# lm386.net
KiCad netlist of a schematic drawn in EAGLE
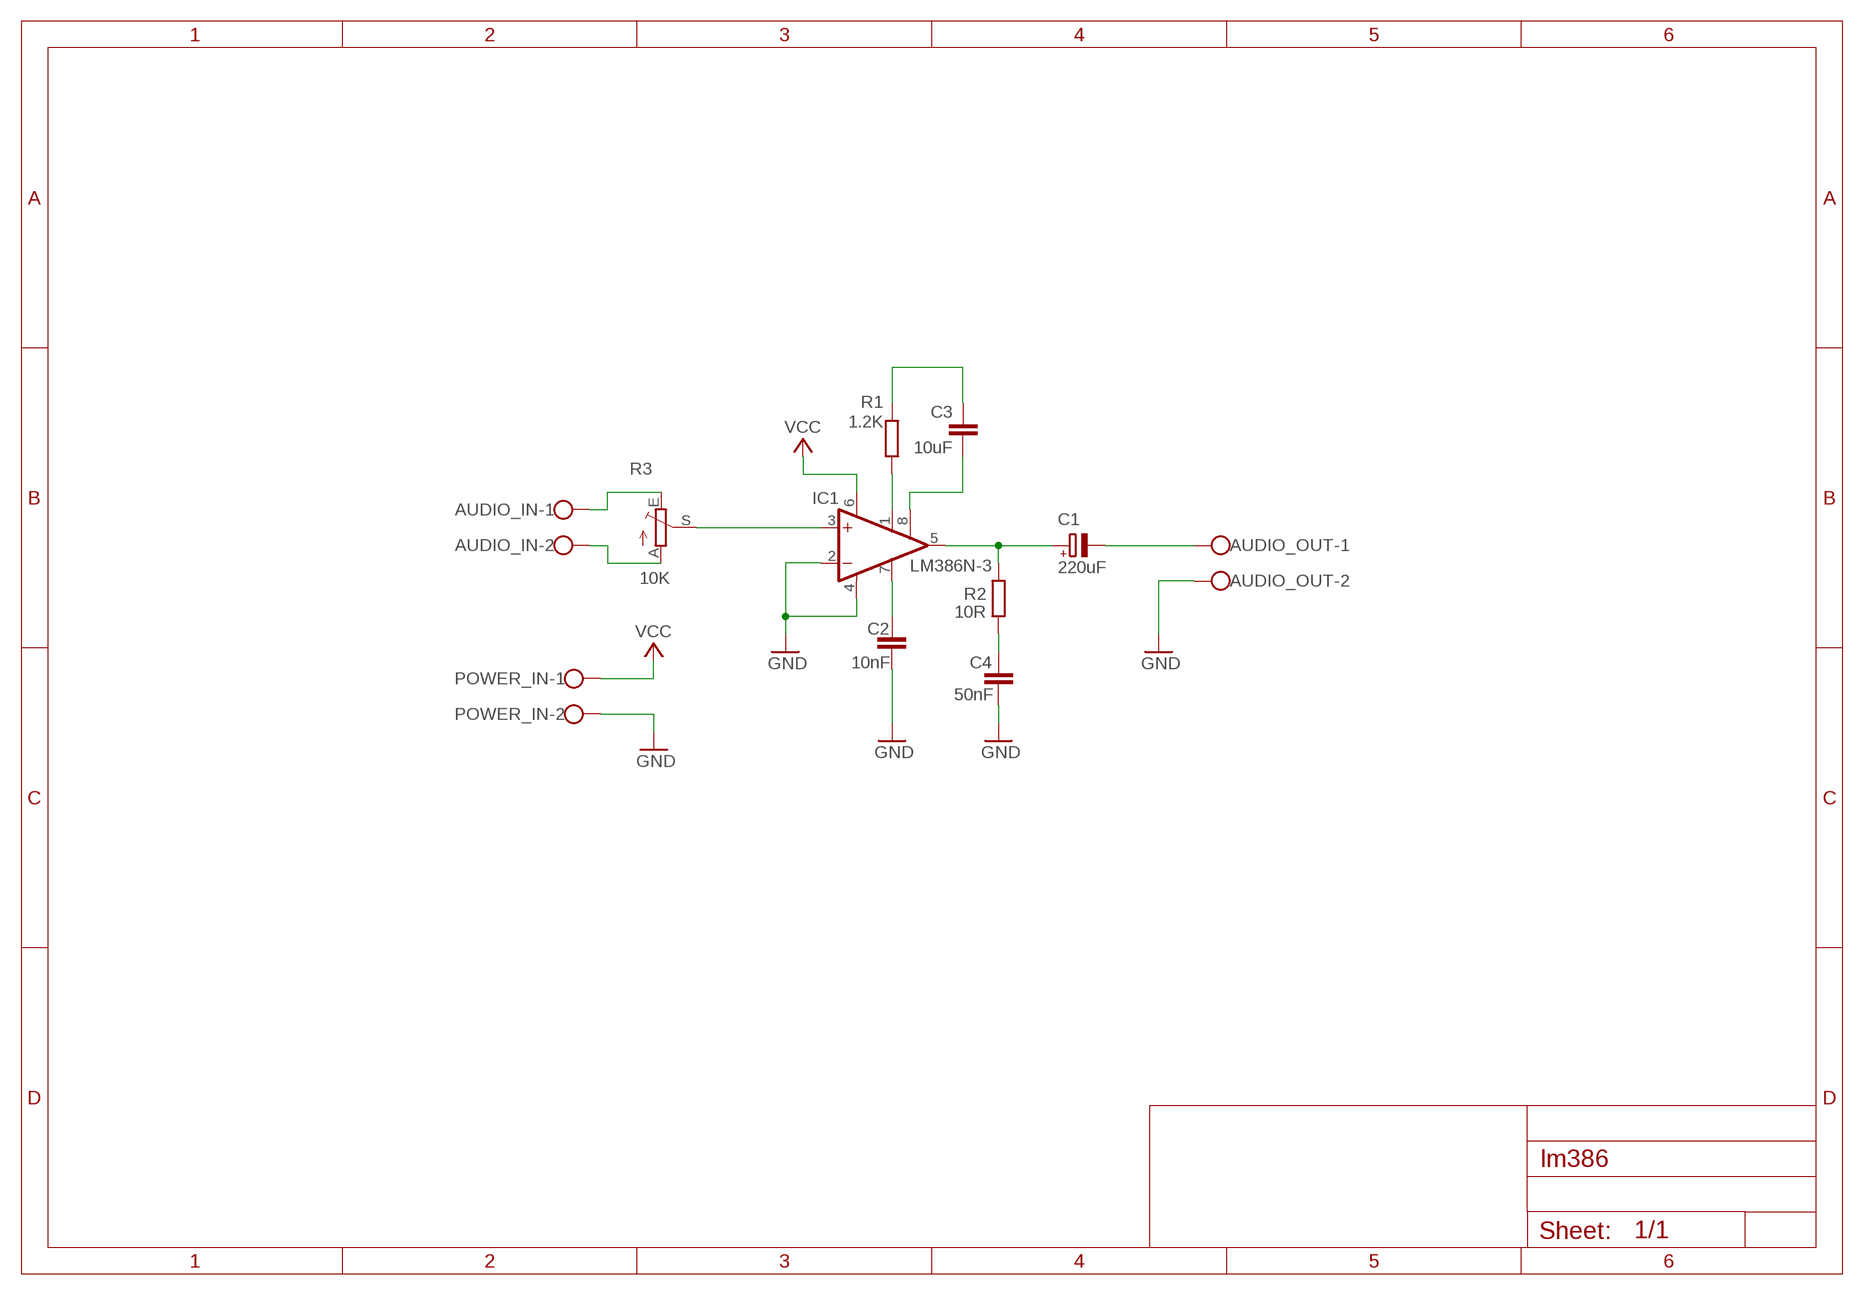
[diagram p0: schematic, sheet 1]

(export (version "E")
  (design (tool "Eeschema 10.0.6"))
  (components
    (comp (ref "AUDIO_IN")
      (value "W237-102")
      (footprint "eagle-import:W237-102")
      (fields (field (name "MPN") "237-102"))
      (libsource (lib "eagle-import") (part "W237-102"))
    )
    (comp (ref "AUDIO_OUT")
      (value "W237-102")
      (footprint "eagle-import:W237-102")
      (fields (field (name "MPN") "237-102"))
      (libsource (lib "eagle-import") (part "W237-102"))
    )
    (comp (ref "C1")
      (value "220uF")
      (footprint "eagle-import:E3,5-8")
      (libsource (lib "eagle-import") (part "CPOL-EUE3.5-8"))
    )
    (comp (ref "C2")
      (value "10nF")
      (footprint "eagle-import:C025-025X050")
      (libsource (lib "eagle-import") (part "C-EU025-025X050"))
    )
    (comp (ref "C3")
      (value "10uF")
      (footprint "eagle-import:C075-032X103")
      (libsource (lib "eagle-import") (part "C-EU075-032X103"))
    )
    (comp (ref "C4")
      (value "50nF")
      (footprint "eagle-import:C025-025X050")
      (libsource (lib "eagle-import") (part "C-EU025-025X050"))
    )
    (comp (ref "IC1")
      (value "LM386N-3")
      (footprint "eagle-import:DIL08")
      (libsource (lib "eagle-import") (part "LM386?-N3"))
    )
    (comp (ref "POWER_IN")
      (value "W237-102")
      (footprint "eagle-import:W237-102")
      (fields (field (name "MPN") "237-102"))
      (libsource (lib "eagle-import") (part "W237-102"))
    )
    (comp (ref "R1")
      (value "1.2K")
      (footprint "eagle-import:0204_7")
      (libsource (lib "eagle-import") (part "R-EU_0204/7"))
    )
    (comp (ref "R2")
      (value "10R")
      (footprint "eagle-import:0204_7")
      (libsource (lib "eagle-import") (part "R-EU_0204/7"))
    )
    (comp (ref "R3")
      (value "10K")
      (footprint "eagle-import:B64Y")
      (libsource (lib "eagle-import") (part "TRIM_EU-B64Y"))
    )
  )
  (nets
    (net (code "1") (name "GND") (class "Default")
      (node (ref "AUDIO_OUT") (pin "2") (pinfunction "KL_2") (pintype "passive"))
      (node (ref "C2") (pin "1") (pinfunction "1_1") (pintype "passive"))
      (node (ref "C4") (pin "2") (pinfunction "2_2") (pintype "passive"))
      (node (ref "IC1") (pin "2") (pinfunction "-IN_2") (pintype "input"))
      (node (ref "IC1") (pin "4") (pinfunction "GND_4") (pintype "power_in"))
      (node (ref "POWER_IN") (pin "2") (pinfunction "KL_2") (pintype "passive"))
    )
    (net (code "2") (name "Net-(AUDIO_INA-KL)") (class "Default")
      (node (ref "AUDIO_IN") (pin "1") (pinfunction "KL_1") (pintype "passive"))
      (node (ref "R3") (pin "E") (pinfunction "E_E") (pintype "passive"))
    )
    (net (code "3") (name "Net-(AUDIO_INB-KL)") (class "Default")
      (node (ref "AUDIO_IN") (pin "2") (pinfunction "KL_2") (pintype "passive"))
      (node (ref "R3") (pin "A") (pinfunction "A_A") (pintype "passive"))
    )
    (net (code "4") (name "Net-(AUDIO_OUTA-KL)") (class "Default")
      (node (ref "AUDIO_OUT") (pin "1") (pinfunction "KL_1") (pintype "passive"))
      (node (ref "C1") (pin "-") (pinfunction "-_-") (pintype "passive"))
    )
    (net (code "5") (name "Net-(C3-Pad1)") (class "Default")
      (node (ref "C3") (pin "1") (pinfunction "1_1") (pintype "passive"))
      (node (ref "IC1") (pin "8") (pinfunction "GAIN_8") (pintype "passive"))
    )
    (net (code "6") (name "Net-(C3-Pad2)") (class "Default")
      (node (ref "C3") (pin "2") (pinfunction "2_2") (pintype "passive"))
      (node (ref "R1") (pin "2") (pinfunction "2_2") (pintype "passive"))
    )
    (net (code "7") (name "Net-(C4-Pad1)") (class "Default")
      (node (ref "C4") (pin "1") (pinfunction "1_1") (pintype "passive"))
      (node (ref "R2") (pin "1") (pinfunction "1_1") (pintype "passive"))
    )
    (net (code "8") (name "Net-(IC1-+IN)") (class "Default")
      (node (ref "IC1") (pin "3") (pinfunction "+IN_3") (pintype "input"))
      (node (ref "R3") (pin "S") (pinfunction "S_S") (pintype "passive"))
    )
    (net (code "9") (name "Net-(IC1-BYPASS)") (class "Default")
      (node (ref "C2") (pin "2") (pinfunction "2_2") (pintype "passive"))
      (node (ref "IC1") (pin "7") (pinfunction "BYPASS_7") (pintype "passive"))
    )
    (net (code "10") (name "Net-(IC1-GAIN-Pad1)") (class "Default")
      (node (ref "IC1") (pin "1") (pinfunction "GAIN_1") (pintype "passive"))
      (node (ref "R1") (pin "1") (pinfunction "1_1") (pintype "passive"))
    )
    (net (code "11") (name "Net-(IC1-OUT)") (class "Default")
      (node (ref "C1") (pin "+") (pinfunction "+_+") (pintype "passive"))
      (node (ref "IC1") (pin "5") (pinfunction "OUT_5") (pintype "output"))
      (node (ref "R2") (pin "2") (pinfunction "2_2") (pintype "passive"))
    )
    (net (code "12") (name "VCC") (class "Default")
      (node (ref "IC1") (pin "6") (pinfunction "VS_6") (pintype "power_in"))
      (node (ref "POWER_IN") (pin "1") (pinfunction "KL_1") (pintype "passive"))
    )
  )
)
